# TPA3122_Class-D.net
KiCad netlist of a schematic drawn in EAGLE
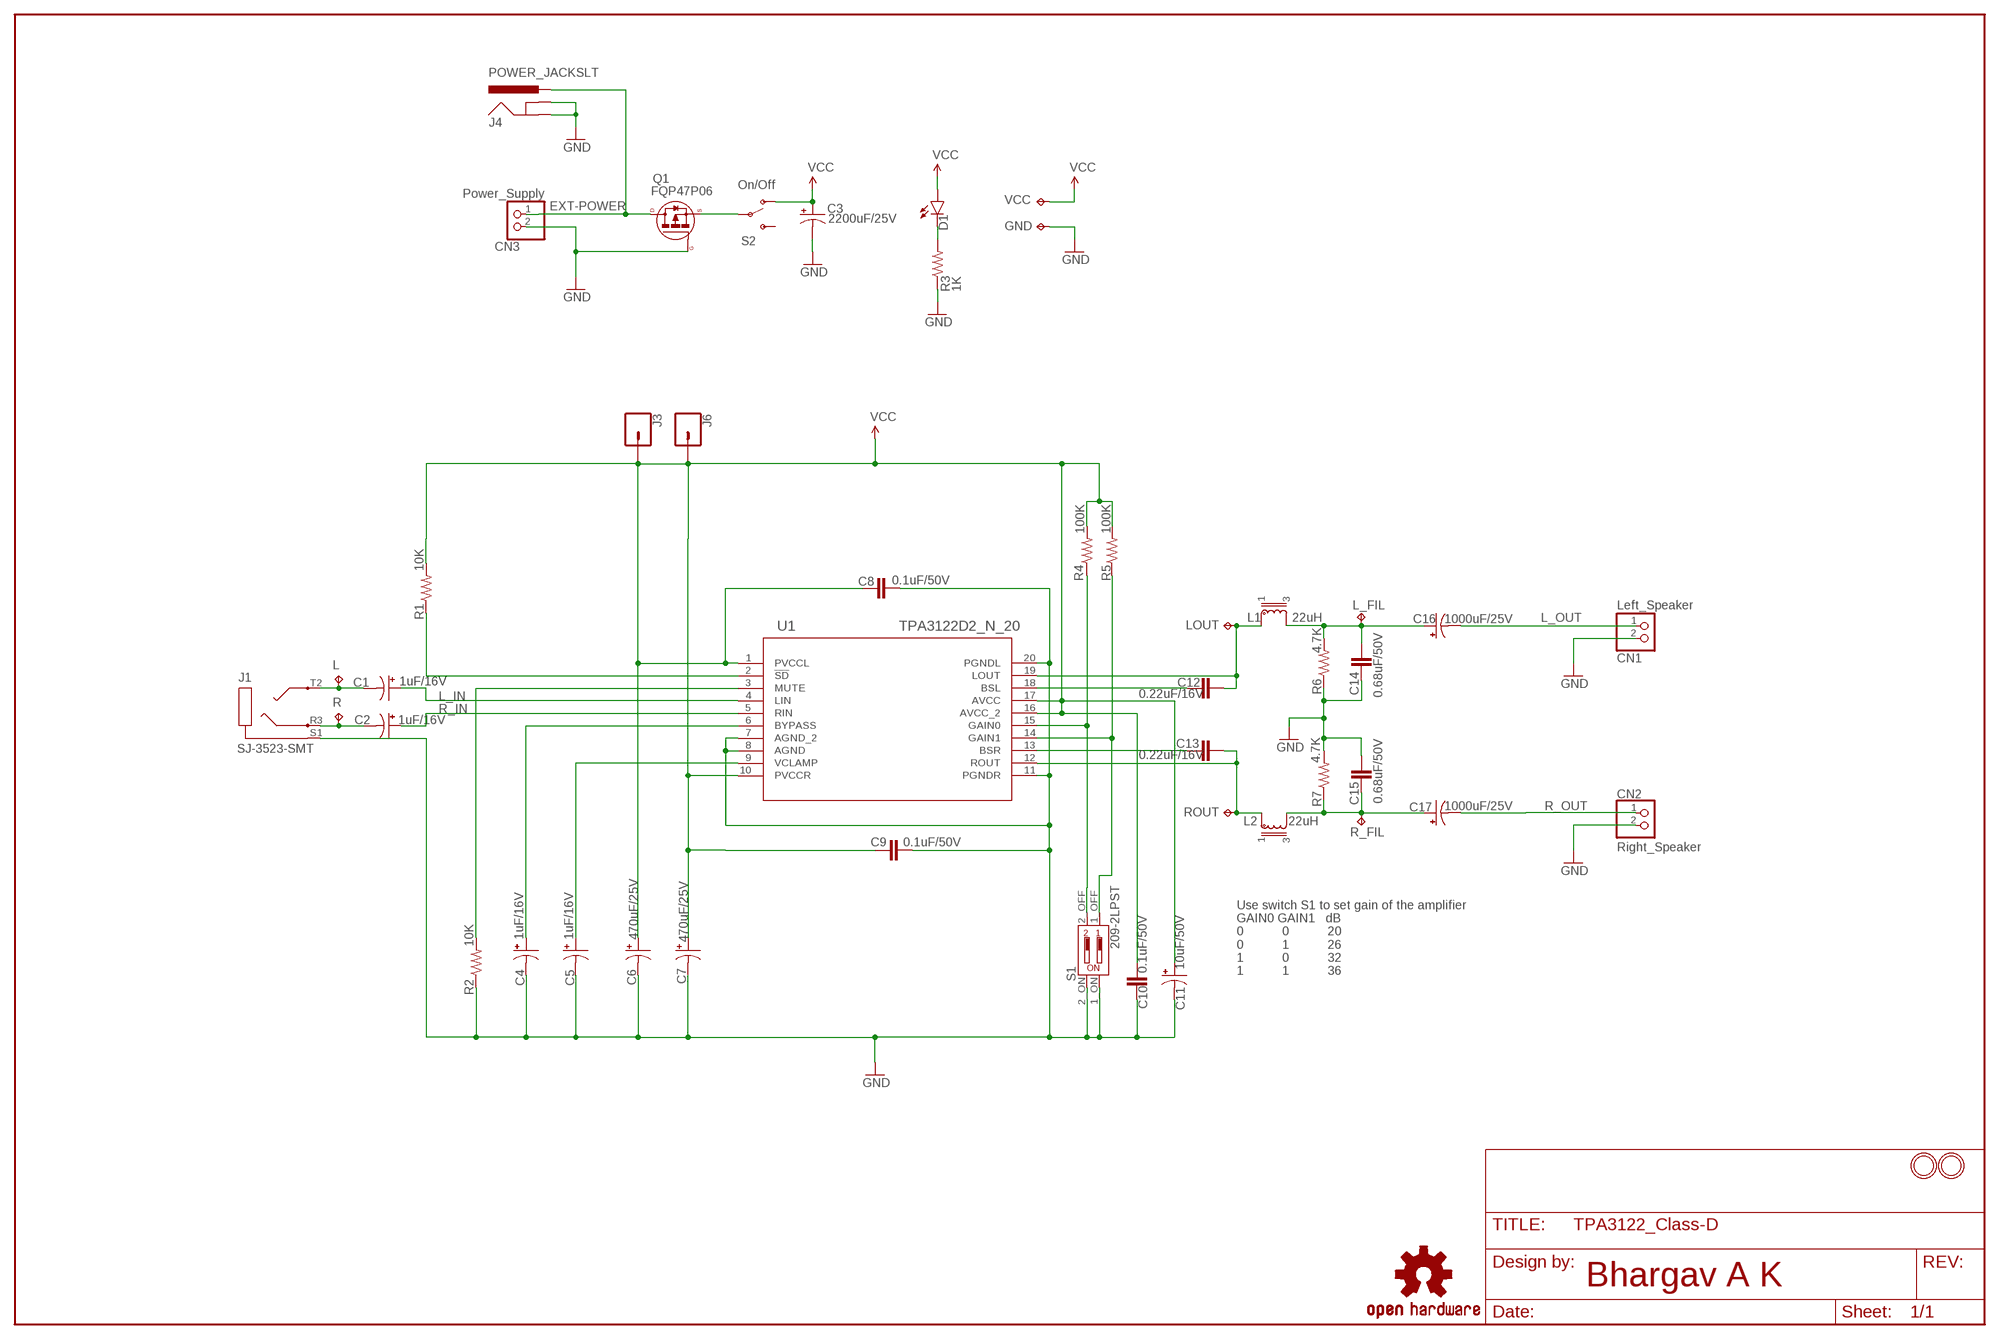
[diagram p0: schematic, sheet 1]

(export (version "E")
  (design (tool "Eeschema 10.0.6"))
  (components
    (comp (ref "C1")
      (value "1uF/16V")
      (footprint "eagle-import:E2,5-5")
      (libsource (lib "eagle-import") (part "CPOL-USE2.5-5"))
    )
    (comp (ref "C2")
      (value "1uF/16V")
      (footprint "eagle-import:E2,5-5")
      (libsource (lib "eagle-import") (part "CPOL-USE2.5-5"))
    )
    (comp (ref "C3")
      (value "2200uF/25V")
      (footprint "eagle-import:E5-13")
      (libsource (lib "eagle-import") (part "CPOL-USE5-13"))
    )
    (comp (ref "C4")
      (value "1uF/16V")
      (footprint "eagle-import:E2,5-5")
      (libsource (lib "eagle-import") (part "CPOL-USE2.5-5"))
    )
    (comp (ref "C5")
      (value "1uF/16V")
      (footprint "eagle-import:E2,5-5")
      (libsource (lib "eagle-import") (part "CPOL-USE2.5-5"))
    )
    (comp (ref "C6")
      (value "470uF/25V")
      (footprint "eagle-import:E5-10,5")
      (libsource (lib "eagle-import") (part "CPOL-USE5-10.5"))
    )
    (comp (ref "C7")
      (value "470uF/25V")
      (footprint "eagle-import:E5-10,5")
      (libsource (lib "eagle-import") (part "CPOL-USE5-10.5"))
    )
    (comp (ref "C8")
      (value "0.1uF/50V")
      (footprint "eagle-import:C050-024X044")
      (libsource (lib "eagle-import") (part "C-EU050-024X044"))
    )
    (comp (ref "C9")
      (value "0.1uF/50V")
      (footprint "eagle-import:C050-024X044")
      (libsource (lib "eagle-import") (part "C-EU050-024X044"))
    )
    (comp (ref "C10")
      (value "0.1uF/50V")
      (footprint "eagle-import:C050-024X044")
      (libsource (lib "eagle-import") (part "C-EU050-024X044"))
    )
    (comp (ref "C11")
      (value "10uF/50V")
      (footprint "eagle-import:E2,5-5")
      (libsource (lib "eagle-import") (part "CPOL-USE2.5-5"))
    )
    (comp (ref "C12")
      (value "0.22uF/16V")
      (footprint "eagle-import:C050-024X044")
      (libsource (lib "eagle-import") (part "C-EU050-024X044"))
    )
    (comp (ref "C13")
      (value "0.22uF/16V")
      (footprint "eagle-import:C050-024X044")
      (libsource (lib "eagle-import") (part "C-EU050-024X044"))
    )
    (comp (ref "C14")
      (value "0.68uF/50V")
      (footprint "eagle-import:C050-024X044")
      (libsource (lib "eagle-import") (part "C-EU050-024X044"))
    )
    (comp (ref "C15")
      (value "0.68uF/50V")
      (footprint "eagle-import:C050-024X044")
      (libsource (lib "eagle-import") (part "C-EU050-024X044"))
    )
    (comp (ref "C16")
      (value "1000uF/25V")
      (footprint "eagle-import:E5-10,5")
      (libsource (lib "eagle-import") (part "CPOL-USE5-10.5"))
    )
    (comp (ref "C17")
      (value "1000uF/25V")
      (footprint "eagle-import:E5-10,5")
      (libsource (lib "eagle-import") (part "CPOL-USE5-10.5"))
    )
    (comp (ref "CN1")
      (value "Left_Speaker")
      (footprint "eagle-import:JST-PH-2-THM")
      (libsource (lib "eagle-import") (part "JST_2PIN-THM"))
    )
    (comp (ref "CN2")
      (value "Right_Speaker")
      (footprint "eagle-import:JST-PH-2-THM")
      (libsource (lib "eagle-import") (part "JST_2PIN-THM"))
    )
    (comp (ref "CN3")
      (value "Power_Supply")
      (footprint "eagle-import:JST-PH-2-THM")
      (libsource (lib "eagle-import") (part "JST_2PIN-THM"))
    )
    (comp (ref "D1")
      (value "LED3MM")
      (footprint "eagle-import:LED_3MM")
      (libsource (lib "eagle-import") (part "LED3MM"))
    )
    (comp (ref "GND")
      (value "TPB2,54")
      (footprint "eagle-import:B2,54")
      (libsource (lib "eagle-import") (part "TPB2,54"))
    )
    (comp (ref "J1")
      (value "SJ-3523-SMT")
      (footprint "eagle-import:SJ-3523-SMT")
      (fields (field (name "MANUFACTURER") "CUI Inc"))
      (libsource (lib "eagle-import") (part "SJ-3523-SMT"))
    )
    (comp (ref "J3")
      (value "CONN_01")
      (footprint "eagle-import:1X01")
      (libsource (lib "eagle-import") (part "CONN_01"))
    )
    (comp (ref "J4")
      (value "POWER_JACKSLT")
      (footprint "eagle-import:POWER_JACK_SLOT")
      (libsource (lib "eagle-import") (part "POWER_JACKSLT"))
    )
    (comp (ref "J6")
      (value "CONN_01")
      (footprint "eagle-import:1X01")
      (libsource (lib "eagle-import") (part "CONN_01"))
    )
    (comp (ref "L")
      (value "TPB2,54")
      (footprint "eagle-import:B2,54")
      (libsource (lib "eagle-import") (part "TPB2,54"))
    )
    (comp (ref "L1")
      (value "22uH")
      (footprint "eagle-import:MURATA_1200RS")
      (libsource (lib "eagle-import") (part "MURATA_1200RS"))
    )
    (comp (ref "L2")
      (value "22uH")
      (footprint "eagle-import:MURATA_1200RS")
      (libsource (lib "eagle-import") (part "MURATA_1200RS"))
    )
    (comp (ref "LOGO1")
      (value "OSHW-LOGOM")
      (footprint "eagle-import:OSHW-LOGO-M")
      (libsource (lib "eagle-import") (part "OSHW-LOGOM"))
    )
    (comp (ref "LOUT")
      (value "TPB2,54")
      (footprint "eagle-import:B2,54")
      (libsource (lib "eagle-import") (part "TPB2,54"))
    )
    (comp (ref "L_FIL")
      (value "TPB2,54")
      (footprint "eagle-import:B2,54")
      (libsource (lib "eagle-import") (part "TPB2,54"))
    )
    (comp (ref "Q1")
      (value "FQP47P06")
      (footprint "eagle-import:TO220")
      (libsource (lib "eagle-import") (part "FQP47P06"))
    )
    (comp (ref "R")
      (value "TPB2,54")
      (footprint "eagle-import:B2,54")
      (libsource (lib "eagle-import") (part "TPB2,54"))
    )
    (comp (ref "R1")
      (value "10K")
      (footprint "eagle-import:0309_10")
      (libsource (lib "eagle-import") (part "R-US_0309/10"))
    )
    (comp (ref "R2")
      (value "10K")
      (footprint "eagle-import:0309_10")
      (libsource (lib "eagle-import") (part "R-US_0309/10"))
    )
    (comp (ref "R3")
      (value "1K")
      (footprint "eagle-import:0309_10")
      (libsource (lib "eagle-import") (part "R-US_0309/10"))
    )
    (comp (ref "R4")
      (value "100K")
      (footprint "eagle-import:0309_10")
      (libsource (lib "eagle-import") (part "R-US_0309/10"))
    )
    (comp (ref "R5")
      (value "100K")
      (footprint "eagle-import:0309_10")
      (libsource (lib "eagle-import") (part "R-US_0309/10"))
    )
    (comp (ref "R6")
      (value "4.7K")
      (footprint "eagle-import:0309_10")
      (libsource (lib "eagle-import") (part "R-US_0309/10"))
    )
    (comp (ref "R7")
      (value "4.7K")
      (footprint "eagle-import:0309_10")
      (libsource (lib "eagle-import") (part "R-US_0309/10"))
    )
    (comp (ref "ROUT")
      (value "TPB2,54")
      (footprint "eagle-import:B2,54")
      (libsource (lib "eagle-import") (part "TPB2,54"))
    )
    (comp (ref "R_FIL")
      (value "TPB2,54")
      (footprint "eagle-import:B2,54")
      (libsource (lib "eagle-import") (part "TPB2,54"))
    )
    (comp (ref "S1")
      (value "209-2LPST")
      (footprint "eagle-import:209-2LPST")
      (libsource (lib "eagle-import") (part "209-2LPST"))
    )
    (comp (ref "S2")
      (value "SWITCH-SPDTPTH")
      (footprint "eagle-import:SWITCH-SPDT")
      (libsource (lib "eagle-import") (part "SWITCH-SPDTPTH"))
    )
    (comp (ref "U$2")
      (value "MOUNTINGHOLE2.5_THICK")
      (footprint "eagle-import:MOUNTINGHOLE_2.5_PLATED_THICK")
      (libsource (lib "eagle-import") (part "MOUNTINGHOLE2.5_THICK"))
    )
    (comp (ref "U$3")
      (value "MOUNTINGHOLE2.5_THICK")
      (footprint "eagle-import:MOUNTINGHOLE_2.5_PLATED_THICK")
      (libsource (lib "eagle-import") (part "MOUNTINGHOLE2.5_THICK"))
    )
    (comp (ref "U1")
      (value "TPA3122D2_N_20")
      (footprint "eagle-import:N20")
      (libsource (lib "eagle-import") (part "TPA3122D2_N_20"))
    )
    (comp (ref "VCC")
      (value "TPB2,54")
      (footprint "eagle-import:B2,54")
      (libsource (lib "eagle-import") (part "TPB2,54"))
    )
  )
  (nets
    (net (code "1") (name "/EXT-POWER") (class "Default")
      (node (ref "CN3") (pin "1") (pinfunction "1_VCC_1") (pintype "passive"))
      (node (ref "J4") (pin "PWR") (pinfunction "PWR_PWR") (pintype "bidirectional"))
      (node (ref "Q1") (pin "D") (pinfunction "D_D") (pintype "passive"))
    )
    (net (code "2") (name "/L_IN") (class "Default")
      (node (ref "C1") (pin "+") (pinfunction "+_+") (pintype "passive"))
      (node (ref "U1") (pin "4") (pinfunction "LIN_4") (pintype "input"))
    )
    (net (code "3") (name "/L_OUT") (class "Default")
      (node (ref "C16") (pin "-") (pinfunction "-_-") (pintype "passive"))
      (node (ref "CN1") (pin "1") (pinfunction "1_VCC_1") (pintype "passive"))
    )
    (net (code "4") (name "/R_IN") (class "Default")
      (node (ref "C2") (pin "+") (pinfunction "+_+") (pintype "passive"))
      (node (ref "U1") (pin "5") (pinfunction "RIN_5") (pintype "input"))
    )
    (net (code "5") (name "/R_OUT") (class "Default")
      (node (ref "C17") (pin "-") (pinfunction "-_-") (pintype "passive"))
      (node (ref "CN2") (pin "1") (pinfunction "1_VCC_1") (pintype "passive"))
    )
    (net (code "6") (name "GND") (class "Default")
      (node (ref "C10") (pin "2") (pinfunction "2_2") (pintype "passive"))
      (node (ref "C11") (pin "-") (pinfunction "-_-") (pintype "passive"))
      (node (ref "C14") (pin "2") (pinfunction "2_2") (pintype "passive"))
      (node (ref "C15") (pin "1") (pinfunction "1_1") (pintype "passive"))
      (node (ref "C3") (pin "-") (pinfunction "-_-") (pintype "passive"))
      (node (ref "C4") (pin "-") (pinfunction "-_-") (pintype "passive"))
      (node (ref "C5") (pin "-") (pinfunction "-_-") (pintype "passive"))
      (node (ref "C6") (pin "-") (pinfunction "-_-") (pintype "passive"))
      (node (ref "C7") (pin "-") (pinfunction "-_-") (pintype "passive"))
      (node (ref "C8") (pin "2") (pinfunction "2_2") (pintype "passive"))
      (node (ref "C9") (pin "2") (pinfunction "2_2") (pintype "passive"))
      (node (ref "CN1") (pin "2") (pinfunction "2_GND_2") (pintype "passive"))
      (node (ref "CN2") (pin "2") (pinfunction "2_GND_2") (pintype "passive"))
      (node (ref "CN3") (pin "2") (pinfunction "2_GND_2") (pintype "passive"))
      (node (ref "GND") (pin "TP") (pinfunction "TP_TP") (pintype "input"))
      (node (ref "J1") (pin "S1") (pinfunction "S1_S1") (pintype "passive"))
      (node (ref "J4") (pin "GND@1") (pinfunction "GNDBREAK_GND@1") (pintype "bidirectional"))
      (node (ref "J4") (pin "GND@2") (pinfunction "GND_GND@2") (pintype "bidirectional"))
      (node (ref "Q1") (pin "G") (pinfunction "G_G") (pintype "passive"))
      (node (ref "R2") (pin "1") (pinfunction "1_1") (pintype "passive"))
      (node (ref "R3") (pin "1") (pinfunction "1_1") (pintype "passive"))
      (node (ref "R6") (pin "1") (pinfunction "1_1") (pintype "passive"))
      (node (ref "R7") (pin "2") (pinfunction "2_2") (pintype "passive"))
      (node (ref "S1") (pin "1_ON") (pinfunction "1_ON_1_ON") (pintype "bidirectional"))
      (node (ref "S1") (pin "2_ON") (pinfunction "2_ON_2_ON") (pintype "bidirectional"))
      (node (ref "U1") (pin "11") (pinfunction "PGNDR_11") (pintype "power_in"))
      (node (ref "U1") (pin "20") (pinfunction "PGNDL_20") (pintype "power_in"))
      (node (ref "U1") (pin "7") (pinfunction "AGND_2_7") (pintype "power_in"))
      (node (ref "U1") (pin "8") (pinfunction "AGND_8") (pintype "power_in"))
    )
    (net (code "7") (name "Net-(C1-Pad-)") (class "Default")
      (node (ref "C1") (pin "-") (pinfunction "-_-") (pintype "passive"))
      (node (ref "J1") (pin "T2") (pinfunction "T2_T2") (pintype "passive"))
      (node (ref "L") (pin "TP") (pinfunction "TP_TP") (pintype "input"))
    )
    (net (code "8") (name "Net-(C2-Pad-)") (class "Default")
      (node (ref "C2") (pin "-") (pinfunction "-_-") (pintype "passive"))
      (node (ref "J1") (pin "R3") (pinfunction "R3_R3") (pintype "passive"))
      (node (ref "R") (pin "TP") (pinfunction "TP_TP") (pintype "input"))
    )
    (net (code "9") (name "Net-(C14-Pad1)") (class "Default")
      (node (ref "C14") (pin "1") (pinfunction "1_1") (pintype "passive"))
      (node (ref "C16") (pin "+") (pinfunction "+_+") (pintype "passive"))
      (node (ref "L1") (pin "3") (pinfunction "3_3") (pintype "passive"))
      (node (ref "L_FIL") (pin "TP") (pinfunction "TP_TP") (pintype "input"))
      (node (ref "R6") (pin "2") (pinfunction "2_2") (pintype "passive"))
    )
    (net (code "10") (name "Net-(C15-Pad2)") (class "Default")
      (node (ref "C15") (pin "2") (pinfunction "2_2") (pintype "passive"))
      (node (ref "C17") (pin "+") (pinfunction "+_+") (pintype "passive"))
      (node (ref "L2") (pin "3") (pinfunction "3_3") (pintype "passive"))
      (node (ref "R7") (pin "1") (pinfunction "1_1") (pintype "passive"))
      (node (ref "R_FIL") (pin "TP") (pinfunction "TP_TP") (pintype "input"))
    )
    (net (code "11") (name "Net-(D1-C)") (class "Default")
      (node (ref "D1") (pin "K") (pinfunction "C_K") (pintype "passive"))
      (node (ref "R3") (pin "2") (pinfunction "2_2") (pintype "passive"))
    )
    (net (code "12") (name "Net-(S2-P)") (class "Default")
      (node (ref "Q1") (pin "S") (pinfunction "S_S") (pintype "passive"))
      (node (ref "S2") (pin "2") (pinfunction "P_2") (pintype "passive"))
    )
    (net (code "13") (name "Net-(U1-BSL)") (class "Default")
      (node (ref "C12") (pin "1") (pinfunction "1_1") (pintype "passive"))
      (node (ref "U1") (pin "18") (pinfunction "BSL_18") (pintype "bidirectional"))
    )
    (net (code "14") (name "Net-(U1-BSR)") (class "Default")
      (node (ref "C13") (pin "1") (pinfunction "1_1") (pintype "passive"))
      (node (ref "U1") (pin "13") (pinfunction "BSR_13") (pintype "bidirectional"))
    )
    (net (code "15") (name "Net-(U1-BYPASS)") (class "Default")
      (node (ref "C4") (pin "+") (pinfunction "+_+") (pintype "passive"))
      (node (ref "U1") (pin "6") (pinfunction "BYPASS_6") (pintype "output"))
    )
    (net (code "16") (name "Net-(U1-GAIN0)") (class "Default")
      (node (ref "R4") (pin "1") (pinfunction "1_1") (pintype "passive"))
      (node (ref "S1") (pin "2_OFF") (pinfunction "2_OFF_2_OFF") (pintype "bidirectional"))
      (node (ref "U1") (pin "15") (pinfunction "GAIN0_15") (pintype "input"))
    )
    (net (code "17") (name "Net-(U1-GAIN1)") (class "Default")
      (node (ref "R5") (pin "1") (pinfunction "1_1") (pintype "passive"))
      (node (ref "S1") (pin "1_OFF") (pinfunction "1_OFF_1_OFF") (pintype "bidirectional"))
      (node (ref "U1") (pin "14") (pinfunction "GAIN1_14") (pintype "input"))
    )
    (net (code "18") (name "Net-(U1-LOUT)") (class "Default")
      (node (ref "C12") (pin "2") (pinfunction "2_2") (pintype "passive"))
      (node (ref "L1") (pin "1") (pinfunction "1_1") (pintype "passive"))
      (node (ref "LOUT") (pin "TP") (pinfunction "TP_TP") (pintype "input"))
      (node (ref "U1") (pin "19") (pinfunction "LOUT_19") (pintype "output"))
    )
    (net (code "19") (name "Net-(U1-MUTE)") (class "Default")
      (node (ref "R2") (pin "2") (pinfunction "2_2") (pintype "passive"))
      (node (ref "U1") (pin "3") (pinfunction "MUTE_3") (pintype "input"))
    )
    (net (code "20") (name "Net-(U1-ROUT)") (class "Default")
      (node (ref "C13") (pin "2") (pinfunction "2_2") (pintype "passive"))
      (node (ref "L2") (pin "1") (pinfunction "1_1") (pintype "passive"))
      (node (ref "ROUT") (pin "TP") (pinfunction "TP_TP") (pintype "input"))
      (node (ref "U1") (pin "12") (pinfunction "ROUT_12") (pintype "output"))
    )
    (net (code "21") (name "Net-(U1-VCLAMP)") (class "Default")
      (node (ref "C5") (pin "+") (pinfunction "+_+") (pintype "passive"))
      (node (ref "U1") (pin "9") (pinfunction "VCLAMP_9") (pintype "power_in"))
    )
    (net (code "22") (name "Net-(U1-~{SD})") (class "Default")
      (node (ref "R1") (pin "1") (pinfunction "1_1") (pintype "passive"))
      (node (ref "U1") (pin "2") (pinfunction "~{SD}_2") (pintype "input"))
    )
    (net (code "23") (name "VCC") (class "Default")
      (node (ref "C10") (pin "1") (pinfunction "1_1") (pintype "passive"))
      (node (ref "C11") (pin "+") (pinfunction "+_+") (pintype "passive"))
      (node (ref "C3") (pin "+") (pinfunction "+_+") (pintype "passive"))
      (node (ref "C6") (pin "+") (pinfunction "+_+") (pintype "passive"))
      (node (ref "C7") (pin "+") (pinfunction "+_+") (pintype "passive"))
      (node (ref "C8") (pin "1") (pinfunction "1_1") (pintype "passive"))
      (node (ref "C9") (pin "1") (pinfunction "1_1") (pintype "passive"))
      (node (ref "D1") (pin "A") (pinfunction "A_A") (pintype "passive"))
      (node (ref "J3") (pin "1") (pinfunction "1_1") (pintype "passive"))
      (node (ref "J6") (pin "1") (pinfunction "1_1") (pintype "passive"))
      (node (ref "R1") (pin "2") (pinfunction "2_2") (pintype "passive"))
      (node (ref "R4") (pin "2") (pinfunction "2_2") (pintype "passive"))
      (node (ref "R5") (pin "2") (pinfunction "2_2") (pintype "passive"))
      (node (ref "S2") (pin "1") (pinfunction "O_1") (pintype "passive"))
      (node (ref "U1") (pin "1") (pinfunction "PVCCL_1") (pintype "power_in"))
      (node (ref "U1") (pin "10") (pinfunction "PVCCR_10") (pintype "power_in"))
      (node (ref "U1") (pin "16") (pinfunction "AVCC_2_16") (pintype "power_in"))
      (node (ref "U1") (pin "17") (pinfunction "AVCC_17") (pintype "power_in"))
      (node (ref "VCC") (pin "TP") (pinfunction "TP_TP") (pintype "input"))
    )
    (net (code "24") (name "unconnected-(S2-S-Pad3)") (class "Default")
      (node (ref "S2") (pin "3") (pinfunction "S_3") (pintype "passive"))
    )
  )
)
